# Tester_V1.net
KiCad netlist of a schematic drawn in EAGLE
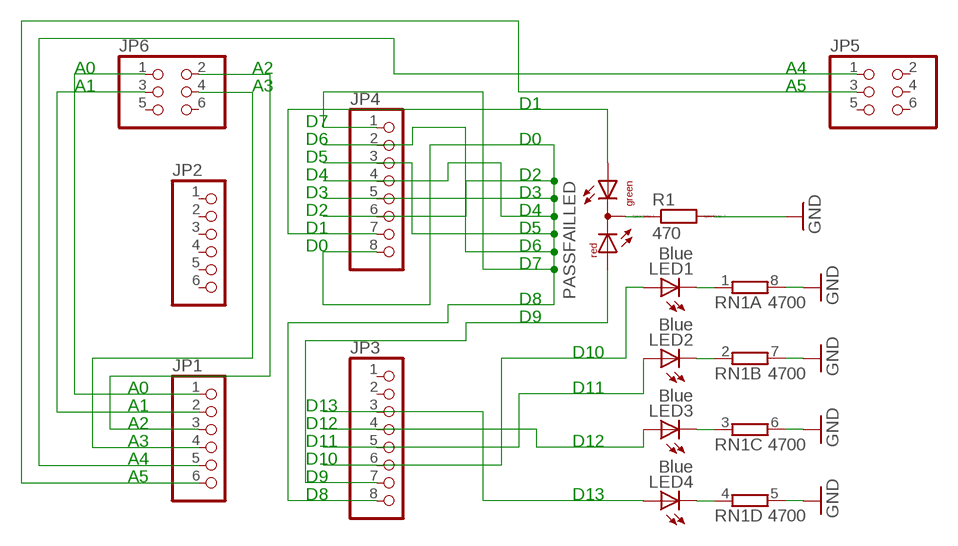
[diagram p0: schematic, sheet 1]

(export (version "E")
  (design (tool "Eeschema 10.0.6"))
  (components
    (comp (ref "JP1")
      (value "PINHD-1X6")
      (footprint "eagle-import:1X06")
      (libsource (lib "eagle-import") (part "PINHD-1X6"))
    )
    (comp (ref "JP2")
      (value "PINHD-1X6")
      (footprint "eagle-import:1X06")
      (libsource (lib "eagle-import") (part "PINHD-1X6"))
    )
    (comp (ref "JP3")
      (value "PINHD-1X8")
      (footprint "eagle-import:1X08")
      (libsource (lib "eagle-import") (part "PINHD-1X8"))
    )
    (comp (ref "JP4")
      (value "PINHD-1X8")
      (footprint "eagle-import:1X08")
      (libsource (lib "eagle-import") (part "PINHD-1X8"))
    )
    (comp (ref "JP5")
      (value "PINHD-2X3")
      (footprint "eagle-import:2X03")
      (libsource (lib "eagle-import") (part "PINHD-2X3"))
    )
    (comp (ref "JP6")
      (value "PINHD-2X3")
      (footprint "eagle-import:2X03")
      (libsource (lib "eagle-import") (part "PINHD-2X3"))
    )
    (comp (ref "LED1")
      (value "Blue")
      (footprint "eagle-import:SMARTLED-TTW")
      (libsource (lib "eagle-import") (part "LED"))
    )
    (comp (ref "LED2")
      (value "Blue")
      (footprint "eagle-import:SMARTLED-TTW")
      (libsource (lib "eagle-import") (part "LED"))
    )
    (comp (ref "LED3")
      (value "Blue")
      (footprint "eagle-import:SMARTLED-TTW")
      (libsource (lib "eagle-import") (part "LED"))
    )
    (comp (ref "LED4")
      (value "Blue")
      (footprint "eagle-import:SMARTLED-TTW")
      (libsource (lib "eagle-import") (part "LED"))
    )
    (comp (ref "PASSFAILLED")
      (value "DUOLED-RG-C")
      (footprint "eagle-import:DUOLED-C-5MM")
      (libsource (lib "eagle-import") (part "DUOLED-RG-C"))
    )
    (comp (ref "R1")
      (value "470")
      (footprint "eagle-import:R0805")
      (libsource (lib "eagle-import") (part "R"))
    )
    (comp (ref "RN1")
      (value "4700")
      (footprint "eagle-import:0603-ARV")
      (libsource (lib "eagle-import") (part "4R-N0603-ARV"))
    )
  )
  (nets
    (net (code "1") (name "GND") (class "Default")
      (node (ref "R1") (pin "2") (pinfunction "2_2") (pintype "passive"))
      (node (ref "RN1") (pin "5") (pinfunction "2_5") (pintype "passive"))
      (node (ref "RN1") (pin "6") (pinfunction "2_6") (pintype "passive"))
      (node (ref "RN1") (pin "7") (pinfunction "2_7") (pintype "passive"))
      (node (ref "RN1") (pin "8") (pinfunction "2_8") (pintype "passive"))
    )
    (net (code "2") (name "Net-(JP1-Pad1)") (class "Default")
      (node (ref "JP1") (pin "1") (pinfunction "1_1") (pintype "passive"))
      (node (ref "JP6") (pin "1") (pinfunction "1_1") (pintype "passive"))
    )
    (net (code "3") (name "Net-(JP1-Pad2)") (class "Default")
      (node (ref "JP1") (pin "2") (pinfunction "2_2") (pintype "passive"))
      (node (ref "JP6") (pin "3") (pinfunction "3_3") (pintype "passive"))
    )
    (net (code "4") (name "Net-(JP1-Pad3)") (class "Default")
      (node (ref "JP1") (pin "3") (pinfunction "3_3") (pintype "passive"))
      (node (ref "JP6") (pin "2") (pinfunction "2_2") (pintype "passive"))
    )
    (net (code "5") (name "Net-(JP1-Pad4)") (class "Default")
      (node (ref "JP1") (pin "4") (pinfunction "4_4") (pintype "passive"))
      (node (ref "JP6") (pin "4") (pinfunction "4_4") (pintype "passive"))
    )
    (net (code "6") (name "Net-(JP1-Pad5)") (class "Default")
      (node (ref "JP1") (pin "5") (pinfunction "5_5") (pintype "passive"))
      (node (ref "JP5") (pin "1") (pinfunction "1_1") (pintype "passive"))
    )
    (net (code "7") (name "Net-(JP1-Pad6)") (class "Default")
      (node (ref "JP1") (pin "6") (pinfunction "6_6") (pintype "passive"))
      (node (ref "JP5") (pin "3") (pinfunction "3_3") (pintype "passive"))
    )
    (net (code "8") (name "Net-(JP3-Pad7)") (class "Default")
      (node (ref "JP3") (pin "7") (pinfunction "7_7") (pintype "passive"))
      (node (ref "PASSFAILLED") (pin "AR") (pinfunction "AR_AR") (pintype "passive"))
    )
    (net (code "9") (name "Net-(JP3-Pad8)") (class "Default")
      (node (ref "JP3") (pin "8") (pinfunction "8_8") (pintype "passive"))
      (node (ref "JP4") (pin "1") (pinfunction "1_1") (pintype "passive"))
      (node (ref "JP4") (pin "2") (pinfunction "2_2") (pintype "passive"))
      (node (ref "JP4") (pin "3") (pinfunction "3_3") (pintype "passive"))
      (node (ref "JP4") (pin "4") (pinfunction "4_4") (pintype "passive"))
      (node (ref "JP4") (pin "5") (pinfunction "5_5") (pintype "passive"))
      (node (ref "JP4") (pin "6") (pinfunction "6_6") (pintype "passive"))
      (node (ref "JP4") (pin "8") (pinfunction "8_8") (pintype "passive"))
    )
    (net (code "10") (name "Net-(LED1-A)") (class "Default")
      (node (ref "JP3") (pin "6") (pinfunction "6_6") (pintype "passive"))
      (node (ref "LED1") (pin "A@1") (pinfunction "A_A@1") (pintype "passive"))
    )
    (net (code "11") (name "Net-(LED1-C)") (class "Default")
      (node (ref "LED1") (pin "C@1") (pinfunction "C_C@1") (pintype "passive"))
      (node (ref "RN1") (pin "1") (pinfunction "1_1") (pintype "passive"))
    )
    (net (code "12") (name "Net-(LED2-A)") (class "Default")
      (node (ref "JP3") (pin "5") (pinfunction "5_5") (pintype "passive"))
      (node (ref "LED2") (pin "A@1") (pinfunction "A_A@1") (pintype "passive"))
    )
    (net (code "13") (name "Net-(LED2-C)") (class "Default")
      (node (ref "LED2") (pin "C@1") (pinfunction "C_C@1") (pintype "passive"))
      (node (ref "RN1") (pin "2") (pinfunction "1_2") (pintype "passive"))
    )
    (net (code "14") (name "Net-(LED3-A)") (class "Default")
      (node (ref "JP3") (pin "4") (pinfunction "4_4") (pintype "passive"))
      (node (ref "LED3") (pin "A@1") (pinfunction "A_A@1") (pintype "passive"))
    )
    (net (code "15") (name "Net-(LED3-C)") (class "Default")
      (node (ref "LED3") (pin "C@1") (pinfunction "C_C@1") (pintype "passive"))
      (node (ref "RN1") (pin "3") (pinfunction "1_3") (pintype "passive"))
    )
    (net (code "16") (name "Net-(LED4-A)") (class "Default")
      (node (ref "JP3") (pin "3") (pinfunction "3_3") (pintype "passive"))
      (node (ref "LED4") (pin "A@1") (pinfunction "A_A@1") (pintype "passive"))
    )
    (net (code "17") (name "Net-(LED4-C)") (class "Default")
      (node (ref "LED4") (pin "C@1") (pinfunction "C_C@1") (pintype "passive"))
      (node (ref "RN1") (pin "4") (pinfunction "1_4") (pintype "passive"))
    )
    (net (code "18") (name "Net-(PASSFAILLED-AG)") (class "Default")
      (node (ref "JP4") (pin "7") (pinfunction "7_7") (pintype "passive"))
      (node (ref "PASSFAILLED") (pin "AX") (pinfunction "AG_AX") (pintype "passive"))
    )
    (net (code "19") (name "Net-(PASSFAILLED-PadC)") (class "Default")
      (node (ref "PASSFAILLED") (pin "C") (pinfunction "C_C") (pintype "passive"))
      (node (ref "R1") (pin "1") (pinfunction "1_1") (pintype "passive"))
    )
    (net (code "20") (name "unconnected-(JP2-Pad1)") (class "Default")
      (node (ref "JP2") (pin "1") (pinfunction "1_1") (pintype "passive"))
    )
    (net (code "21") (name "unconnected-(JP2-Pad2)") (class "Default")
      (node (ref "JP2") (pin "2") (pinfunction "2_2") (pintype "passive"))
    )
    (net (code "22") (name "unconnected-(JP2-Pad3)") (class "Default")
      (node (ref "JP2") (pin "3") (pinfunction "3_3") (pintype "passive"))
    )
    (net (code "23") (name "unconnected-(JP2-Pad4)") (class "Default")
      (node (ref "JP2") (pin "4") (pinfunction "4_4") (pintype "passive"))
    )
    (net (code "24") (name "unconnected-(JP2-Pad5)") (class "Default")
      (node (ref "JP2") (pin "5") (pinfunction "5_5") (pintype "passive"))
    )
    (net (code "25") (name "unconnected-(JP2-Pad6)") (class "Default")
      (node (ref "JP2") (pin "6") (pinfunction "6_6") (pintype "passive"))
    )
    (net (code "26") (name "unconnected-(JP3-Pad1)") (class "Default")
      (node (ref "JP3") (pin "1") (pinfunction "1_1") (pintype "passive"))
    )
    (net (code "27") (name "unconnected-(JP3-Pad2)") (class "Default")
      (node (ref "JP3") (pin "2") (pinfunction "2_2") (pintype "passive"))
    )
    (net (code "28") (name "unconnected-(JP5-Pad2)") (class "Default")
      (node (ref "JP5") (pin "2") (pinfunction "2_2") (pintype "passive"))
    )
    (net (code "29") (name "unconnected-(JP5-Pad4)") (class "Default")
      (node (ref "JP5") (pin "4") (pinfunction "4_4") (pintype "passive"))
    )
    (net (code "30") (name "unconnected-(JP5-Pad5)") (class "Default")
      (node (ref "JP5") (pin "5") (pinfunction "5_5") (pintype "passive"))
    )
    (net (code "31") (name "unconnected-(JP5-Pad6)") (class "Default")
      (node (ref "JP5") (pin "6") (pinfunction "6_6") (pintype "passive"))
    )
    (net (code "32") (name "unconnected-(JP6-Pad5)") (class "Default")
      (node (ref "JP6") (pin "5") (pinfunction "5_5") (pintype "passive"))
    )
    (net (code "33") (name "unconnected-(JP6-Pad6)") (class "Default")
      (node (ref "JP6") (pin "6") (pinfunction "6_6") (pintype "passive"))
    )
  )
)
